# Antenna_sw.net
KiCad netlist of a schematic drawn in Altium Designer
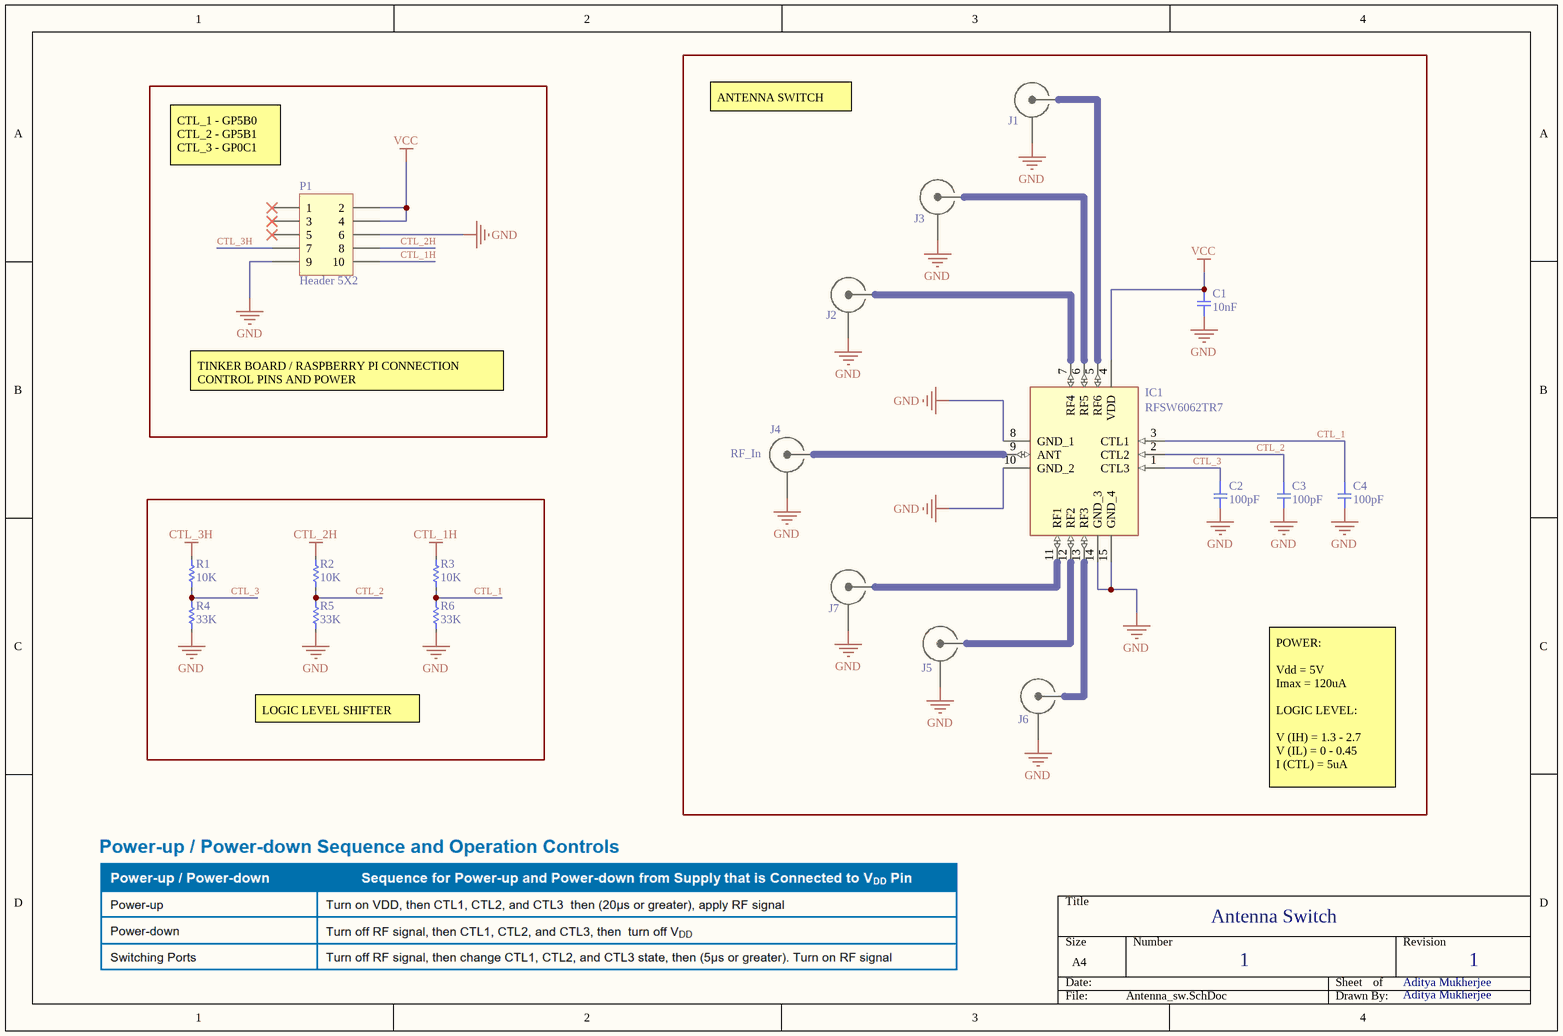
[diagram p0: Antenna_sw.SchDoc]

(export (version "E")
  (design (tool "Eeschema 10.0.6"))
  (components
    (comp (ref "C1")
      (value "10nF")
      (footprint "SMD-0402C")
      (description "CAP CER 1UF 10V X7S 0402")
      (fields
        (field (name "DIGI-KEY PART NUMBER") "490-13409-1-ND")
        (field (name "PART NUMBER") "GCM155C71A105KE38D")
      )
      (libsource (lib "capacitor_murata_0402") (part "GCM155C71A105KE38D"))
    )
    (comp (ref "C2")
      (value "100pF")
      (footprint "SMD-0402C")
      (description "CAP CER 1UF 10V X7S 0402")
      (fields
        (field (name "DIGI-KEY PART NUMBER") "490-13409-1-ND")
        (field (name "PART NUMBER") "GCM155C71A105KE38D")
      )
      (libsource (lib "capacitor_murata_0402") (part "GCM155C71A105KE38D"))
    )
    (comp (ref "C3")
      (value "100pF")
      (footprint "SMD-0402C")
      (description "CAP CER 1UF 10V X7S 0402")
      (fields
        (field (name "DIGI-KEY PART NUMBER") "490-13409-1-ND")
        (field (name "PART NUMBER") "GCM155C71A105KE38D")
      )
      (libsource (lib "capacitor_murata_0402") (part "GCM155C71A105KE38D"))
    )
    (comp (ref "C4")
      (value "100pF")
      (footprint "SMD-0402C")
      (description "CAP CER 1UF 10V X7S 0402")
      (fields
        (field (name "DIGI-KEY PART NUMBER") "490-13409-1-ND")
        (field (name "PART NUMBER") "GCM155C71A105KE38D")
      )
      (libsource (lib "capacitor_murata_0402") (part "GCM155C71A105KE38D"))
    )
    (comp (ref "IC1")
      (value "RFSW6062TR7")
      (footprint "SamacSys:QFN40P200X200X60-15N-D")
      (description "RF Switch")
      (fields (field (name "MOUSER PART NUMBER") "772-RFSW6062"))
      (libsource (lib "*") (part "RFSW6062TR7"))
    )
    (comp (ref "J1")
      (value "SMA_end_launch")
      (footprint "PCBComponent_1")
      (description "Sma end launch female")
      (libsource (lib "SMA_small") (part "Component_1"))
    )
    (comp (ref "J2")
      (value "SMA_end_launch")
      (footprint "PCBComponent_1")
      (description "Sma end launch female")
      (libsource (lib "SMA_small") (part "Component_1"))
    )
    (comp (ref "J3")
      (value "SMA_end_launch")
      (footprint "PCBComponent_1")
      (description "Sma end launch female")
      (libsource (lib "SMA_small") (part "Component_1"))
    )
    (comp (ref "J4")
      (value "RF_In")
      (footprint "PCBComponent_1")
      (description "Sma end launch female")
      (fields (field (name "Comment") "SMA_end_launch"))
      (libsource (lib "") (part "Component_1_1"))
    )
    (comp (ref "J5")
      (value "SMA_end_launch")
      (footprint "PCBComponent_1")
      (description "Sma end launch female")
      (libsource (lib "SMA_small") (part "Component_1"))
    )
    (comp (ref "J6")
      (value "SMA_end_launch")
      (footprint "PCBComponent_1")
      (description "Sma end launch female")
      (libsource (lib "SMA_small") (part "Component_1"))
    )
    (comp (ref "J7")
      (value "SMA_end_launch")
      (footprint "PCBComponent_1")
      (description "Sma end launch female")
      (libsource (lib "SMA_small") (part "Component_1"))
    )
    (comp (ref "P1")
      (value "Header 5X2")
      (footprint "HDR2X5")
      (description "Header, 5-Pin, Dual row")
      (fields (field (name "PUBLISHER") "Altium Limited"))
      (libsource (lib "Miscellaneous Connectors") (part "Header 5X2"))
    )
    (comp (ref "R1")
      (value "10K")
      (footprint "PCBComponent_1")
      (libsource (lib "0402resistor") (part "Component_1"))
    )
    (comp (ref "R2")
      (value "10K")
      (footprint "PCBComponent_1")
      (libsource (lib "0402resistor") (part "Component_1"))
    )
    (comp (ref "R3")
      (value "10K")
      (footprint "PCBComponent_1")
      (libsource (lib "0402resistor") (part "Component_1"))
    )
    (comp (ref "R4")
      (value "33K")
      (footprint "PCBComponent_1")
      (libsource (lib "0402resistor") (part "Component_1"))
    )
    (comp (ref "R5")
      (value "33K")
      (footprint "PCBComponent_1")
      (libsource (lib "0402resistor") (part "Component_1"))
    )
    (comp (ref "R6")
      (value "33K")
      (footprint "PCBComponent_1")
      (libsource (lib "0402resistor") (part "Component_1"))
    )
  )
  (nets
    (net (code "1") (name "/CTL_1") (class "Default")
      (node (ref "C4") (pin "1") (pinfunction "1_1") (pintype "passive"))
      (node (ref "IC1") (pin "3") (pinfunction "CTL1_3") (pintype "input"))
      (node (ref "R3") (pin "1") (pinfunction "1_1") (pintype "passive"))
      (node (ref "R6") (pin "2") (pinfunction "2_2") (pintype "passive"))
    )
    (net (code "2") (name "/CTL_2") (class "Default")
      (node (ref "C3") (pin "1") (pinfunction "1_1") (pintype "passive"))
      (node (ref "IC1") (pin "2") (pinfunction "CTL2_2") (pintype "input"))
      (node (ref "R2") (pin "1") (pinfunction "1_1") (pintype "passive"))
      (node (ref "R5") (pin "2") (pinfunction "2_2") (pintype "passive"))
    )
    (net (code "3") (name "/CTL_3") (class "Default")
      (node (ref "C2") (pin "1") (pinfunction "1_1") (pintype "passive"))
      (node (ref "IC1") (pin "1") (pinfunction "CTL3_1") (pintype "input"))
      (node (ref "R1") (pin "1") (pinfunction "1_1") (pintype "passive"))
      (node (ref "R4") (pin "2") (pinfunction "2_2") (pintype "passive"))
    )
    (net (code "4") (name "CTL_1H") (class "Default")
      (node (ref "P1") (pin "10") (pinfunction "10_10") (pintype "passive"))
      (node (ref "R3") (pin "2") (pinfunction "2_2") (pintype "passive"))
    )
    (net (code "5") (name "CTL_2H") (class "Default")
      (node (ref "P1") (pin "8") (pinfunction "8_8") (pintype "passive"))
      (node (ref "R2") (pin "2") (pinfunction "2_2") (pintype "passive"))
    )
    (net (code "6") (name "CTL_3H") (class "Default")
      (node (ref "P1") (pin "7") (pinfunction "7_7") (pintype "passive"))
      (node (ref "R1") (pin "2") (pinfunction "2_2") (pintype "passive"))
    )
    (net (code "7") (name "GND") (class "Default")
      (node (ref "C1") (pin "2") (pinfunction "2_2") (pintype "passive"))
      (node (ref "C2") (pin "2") (pinfunction "2_2") (pintype "passive"))
      (node (ref "C3") (pin "2") (pinfunction "2_2") (pintype "passive"))
      (node (ref "C4") (pin "2") (pinfunction "2_2") (pintype "passive"))
      (node (ref "IC1") (pin "10") (pinfunction "GND_2_10") (pintype "power_in"))
      (node (ref "IC1") (pin "14") (pinfunction "GND_3_14") (pintype "power_in"))
      (node (ref "IC1") (pin "15") (pinfunction "GND_4_15") (pintype "power_in"))
      (node (ref "IC1") (pin "8") (pinfunction "GND_1_8") (pintype "power_in"))
      (node (ref "J1") (pin "2") (pinfunction "2_2") (pintype "passive"))
      (node (ref "J2") (pin "2") (pinfunction "2_2") (pintype "passive"))
      (node (ref "J3") (pin "2") (pinfunction "2_2") (pintype "passive"))
      (node (ref "J4") (pin "2") (pinfunction "2_2") (pintype "passive"))
      (node (ref "J5") (pin "2") (pinfunction "2_2") (pintype "passive"))
      (node (ref "J6") (pin "2") (pinfunction "2_2") (pintype "passive"))
      (node (ref "J7") (pin "2") (pinfunction "2_2") (pintype "passive"))
      (node (ref "P1") (pin "6") (pinfunction "6_6") (pintype "passive"))
      (node (ref "P1") (pin "9") (pinfunction "9_9") (pintype "passive"))
      (node (ref "R4") (pin "1") (pinfunction "1_1") (pintype "passive"))
      (node (ref "R5") (pin "1") (pinfunction "1_1") (pintype "passive"))
      (node (ref "R6") (pin "1") (pinfunction "1_1") (pintype "passive"))
    )
    (net (code "8") (name "Net-(IC1-ANT)") (class "Default")
      (node (ref "IC1") (pin "9") (pinfunction "ANT_9") (pintype "bidirectional"))
      (node (ref "J4") (pin "1") (pinfunction "1_1") (pintype "passive"))
    )
    (net (code "9") (name "Net-(IC1-RF1)") (class "Default")
      (node (ref "IC1") (pin "11") (pinfunction "RF1_11") (pintype "bidirectional"))
      (node (ref "J7") (pin "1") (pinfunction "1_1") (pintype "passive"))
    )
    (net (code "10") (name "Net-(IC1-RF2)") (class "Default")
      (node (ref "IC1") (pin "12") (pinfunction "RF2_12") (pintype "bidirectional"))
      (node (ref "J5") (pin "1") (pinfunction "1_1") (pintype "passive"))
    )
    (net (code "11") (name "Net-(IC1-RF3)") (class "Default")
      (node (ref "IC1") (pin "13") (pinfunction "RF3_13") (pintype "bidirectional"))
      (node (ref "J6") (pin "1") (pinfunction "1_1") (pintype "passive"))
    )
    (net (code "12") (name "Net-(IC1-RF4)") (class "Default")
      (node (ref "IC1") (pin "7") (pinfunction "RF4_7") (pintype "bidirectional"))
      (node (ref "J2") (pin "1") (pinfunction "1_1") (pintype "passive"))
    )
    (net (code "13") (name "Net-(IC1-RF5)") (class "Default")
      (node (ref "IC1") (pin "6") (pinfunction "RF5_6") (pintype "bidirectional"))
      (node (ref "J3") (pin "1") (pinfunction "1_1") (pintype "passive"))
    )
    (net (code "14") (name "Net-(IC1-RF6)") (class "Default")
      (node (ref "IC1") (pin "5") (pinfunction "RF6_5") (pintype "bidirectional"))
      (node (ref "J1") (pin "1") (pinfunction "1_1") (pintype "passive"))
    )
    (net (code "15") (name "VCC") (class "Default")
      (node (ref "C1") (pin "1") (pinfunction "1_1") (pintype "passive"))
      (node (ref "IC1") (pin "4") (pinfunction "VDD_4") (pintype "power_in"))
      (node (ref "P1") (pin "2") (pinfunction "2_2") (pintype "passive"))
      (node (ref "P1") (pin "4") (pinfunction "4_4") (pintype "passive"))
    )
    (net (code "16") (name "unconnected-(P1-Pad1)") (class "Default")
      (node (ref "P1") (pin "1") (pinfunction "1_1") (pintype "passive+no_connect"))
    )
    (net (code "17") (name "unconnected-(P1-Pad3)") (class "Default")
      (node (ref "P1") (pin "3") (pinfunction "3_3") (pintype "passive+no_connect"))
    )
    (net (code "18") (name "unconnected-(P1-Pad5)") (class "Default")
      (node (ref "P1") (pin "5") (pinfunction "5_5") (pintype "passive+no_connect"))
    )
  )
)
